# working.net
KiCad netlist of a schematic drawn in EAGLE
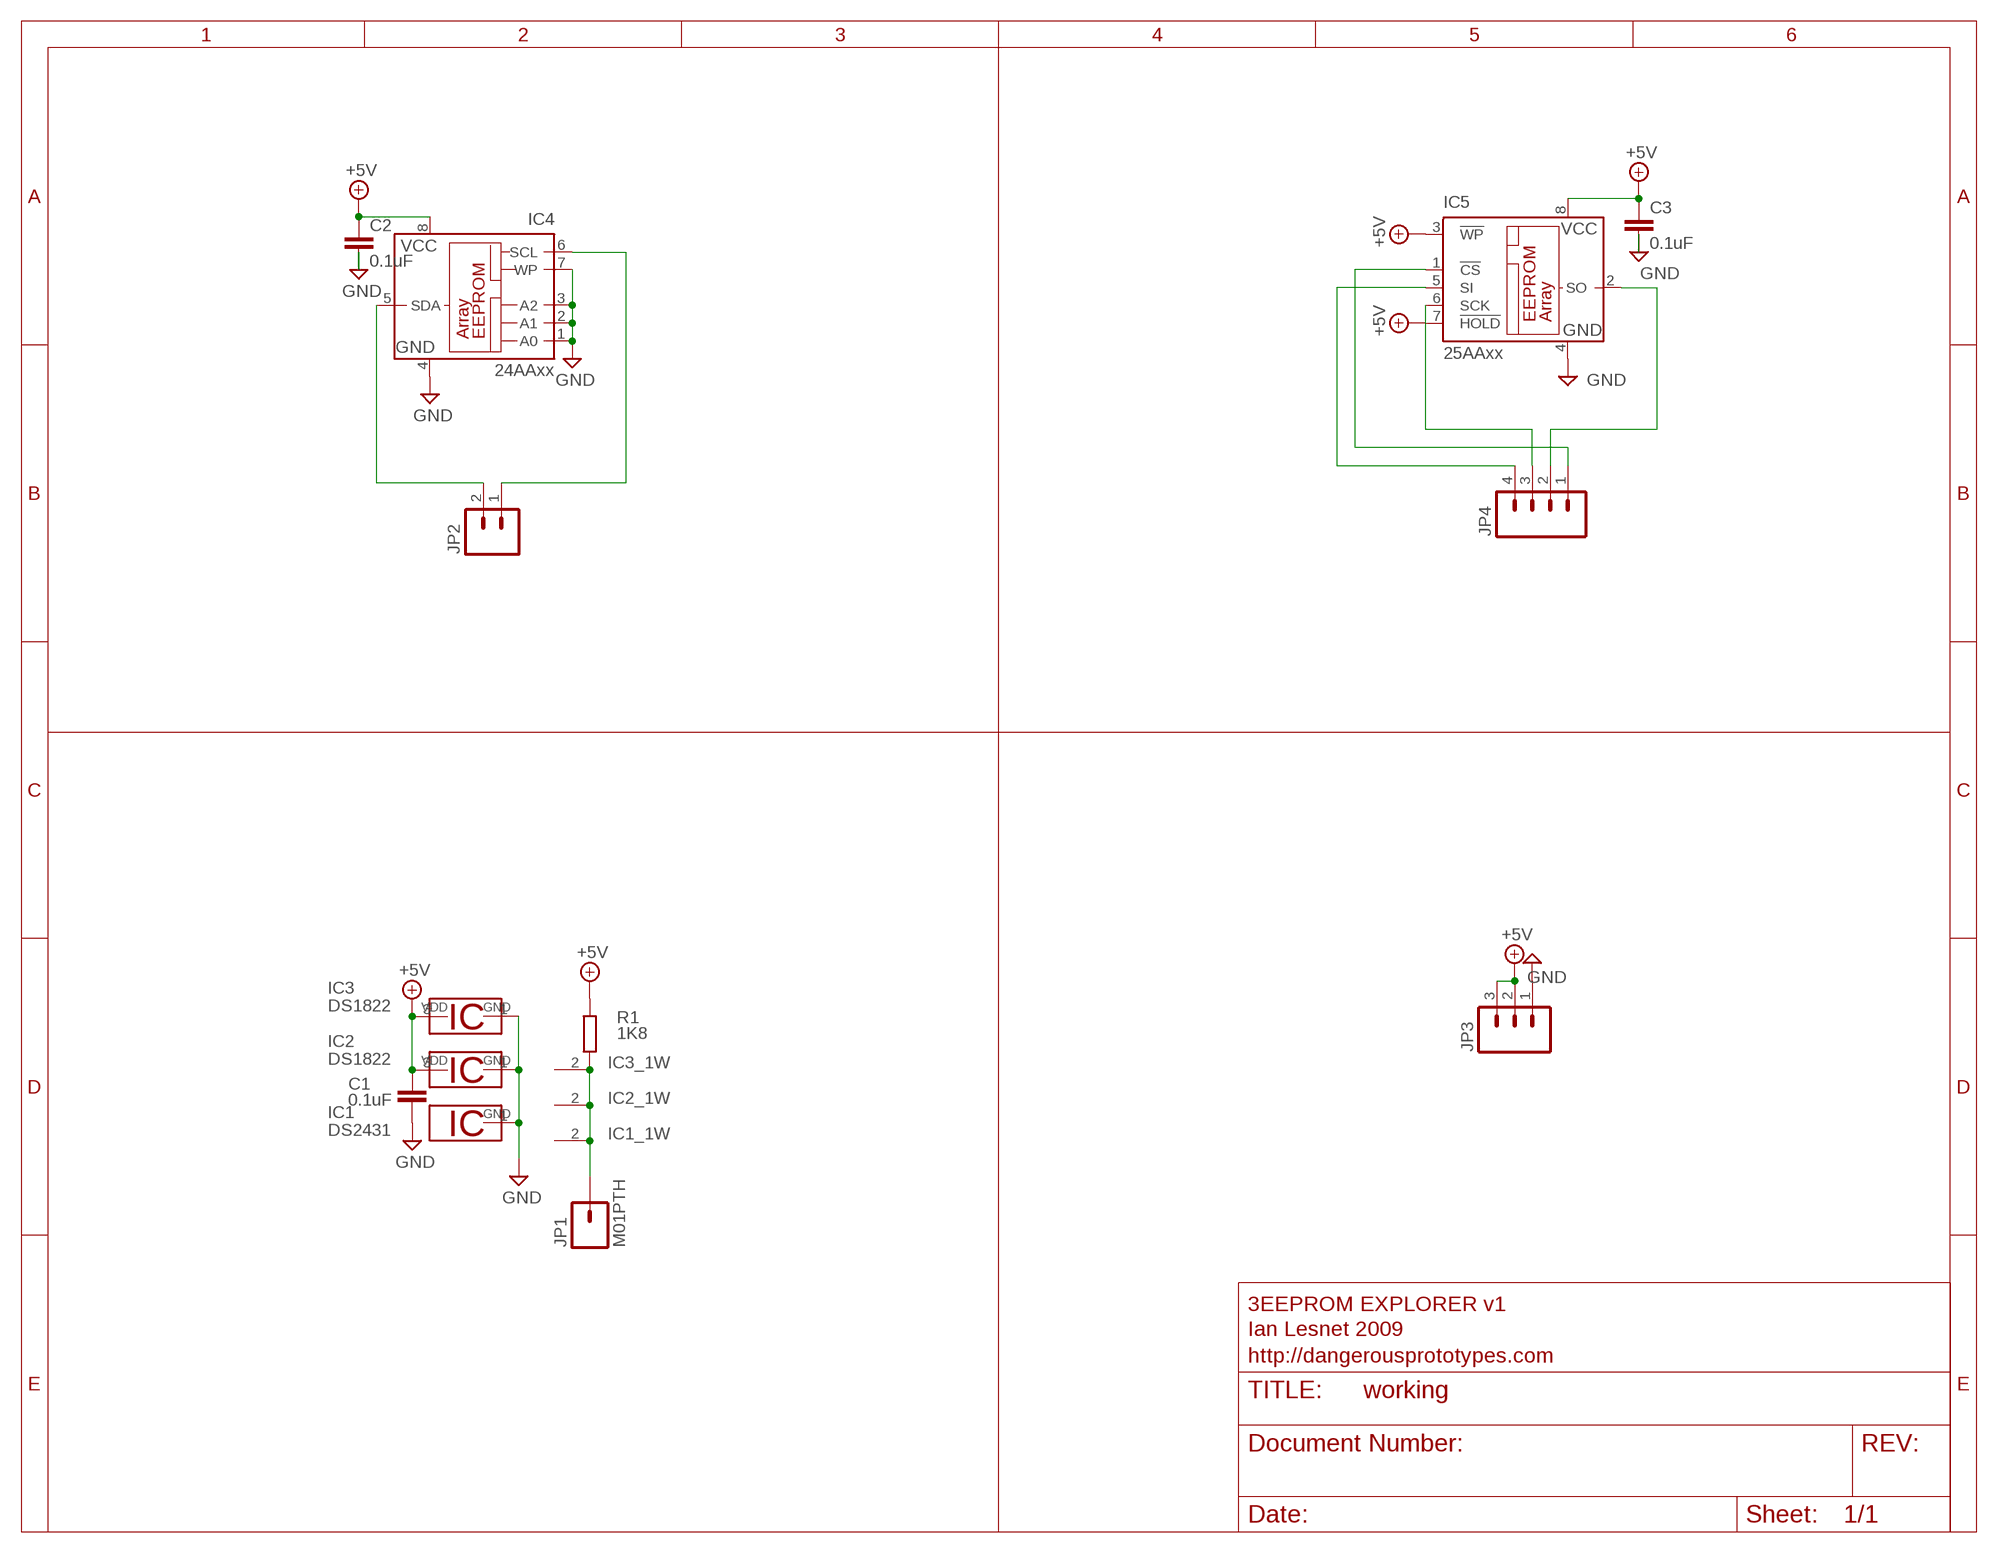
[diagram p0: schematic, sheet 1]

(export (version "E")
  (design (tool "Eeschema 10.0.6"))
  (components
    (comp (ref "C1")
      (value "0.1uF")
      (footprint "eagle-import:C025-025X050")
      (libsource (lib "eagle-import") (part "C-EU025-025X050"))
    )
    (comp (ref "C2")
      (value "0.1uF")
      (footprint "eagle-import:C025-025X050")
      (libsource (lib "eagle-import") (part "C-EU025-025X050"))
    )
    (comp (ref "C3")
      (value "0.1uF")
      (footprint "eagle-import:C025-025X050")
      (libsource (lib "eagle-import") (part "C-EU025-025X050"))
    )
    (comp (ref "IC1")
      (value "DS2431")
      (footprint "eagle-import:TO92-")
      (libsource (lib "eagle-import") (part "DS2431"))
    )
    (comp (ref "IC2")
      (value "DS1822")
      (footprint "eagle-import:TO92-")
      (libsource (lib "eagle-import") (part "DS18S20"))
    )
    (comp (ref "IC3")
      (value "DS1822")
      (footprint "eagle-import:TO92-")
      (libsource (lib "eagle-import") (part "DS18S20"))
    )
    (comp (ref "IC4")
      (value "24AAxx")
      (footprint "eagle-import:DIL8")
      (libsource (lib "eagle-import") (part "24PAA01"))
    )
    (comp (ref "IC5")
      (value "25AAxx")
      (footprint "eagle-import:DIL8")
      (libsource (lib "eagle-import") (part "25PAA040"))
    )
    (comp (ref "JP1")
      (value "M01PTH")
      (footprint "eagle-import:1X01")
      (libsource (lib "eagle-import") (part "M01PTH"))
    )
    (comp (ref "JP2")
      (value "M02PTH")
      (footprint "eagle-import:1X02")
      (libsource (lib "eagle-import") (part "M02PTH"))
    )
    (comp (ref "JP3")
      (value "M03PTH")
      (footprint "eagle-import:1X03")
      (libsource (lib "eagle-import") (part "M03PTH"))
    )
    (comp (ref "JP4")
      (value "M04PTH")
      (footprint "eagle-import:1X04")
      (libsource (lib "eagle-import") (part "M04PTH"))
    )
    (comp (ref "R1")
      (value "1K8")
      (footprint "eagle-import:0204_5")
      (libsource (lib "eagle-import") (part "R-EU_0204/5"))
    )
  )
  (nets
    (net (code "1") (name "+5V") (class "Default")
      (node (ref "C1") (pin "1") (pinfunction "1_1") (pintype "passive"))
      (node (ref "C2") (pin "1") (pinfunction "1_1") (pintype "passive"))
      (node (ref "C3") (pin "1") (pinfunction "1_1") (pintype "passive"))
      (node (ref "IC2") (pin "3") (pinfunction "VDD_3") (pintype "power_in"))
      (node (ref "IC3") (pin "3") (pinfunction "VDD_3") (pintype "power_in"))
      (node (ref "IC4") (pin "8") (pinfunction "VCC_8") (pintype "power_in"))
      (node (ref "IC5") (pin "3") (pinfunction "~{WP}_3") (pintype "input"))
      (node (ref "IC5") (pin "7") (pinfunction "~{HOLD}_7") (pintype "input"))
      (node (ref "IC5") (pin "8") (pinfunction "VCC_8") (pintype "power_in"))
      (node (ref "JP3") (pin "2") (pinfunction "2_2") (pintype "passive"))
      (node (ref "JP3") (pin "3") (pinfunction "3_3") (pintype "passive"))
      (node (ref "R1") (pin "2") (pinfunction "2_2") (pintype "passive"))
    )
    (net (code "2") (name "GND") (class "Default")
      (node (ref "C1") (pin "2") (pinfunction "2_2") (pintype "passive"))
      (node (ref "C2") (pin "2") (pinfunction "2_2") (pintype "passive"))
      (node (ref "C3") (pin "2") (pinfunction "2_2") (pintype "passive"))
      (node (ref "IC1") (pin "1") (pinfunction "GND_1") (pintype "power_in"))
      (node (ref "IC2") (pin "1") (pinfunction "GND_1") (pintype "power_in"))
      (node (ref "IC3") (pin "1") (pinfunction "GND_1") (pintype "power_in"))
      (node (ref "IC4") (pin "1") (pinfunction "A0_1") (pintype "input"))
      (node (ref "IC4") (pin "2") (pinfunction "A1_2") (pintype "input"))
      (node (ref "IC4") (pin "3") (pinfunction "A2_3") (pintype "input"))
      (node (ref "IC4") (pin "4") (pinfunction "GND_4") (pintype "power_in"))
      (node (ref "IC4") (pin "7") (pinfunction "WP_7") (pintype "input"))
      (node (ref "IC5") (pin "4") (pinfunction "GND_4") (pintype "power_in"))
      (node (ref "JP3") (pin "1") (pinfunction "1_1") (pintype "passive"))
    )
    (net (code "3") (name "Net-(IC1C-1W)") (class "Default")
      (node (ref "IC1") (pin "2") (pinfunction "1W_2") (pintype "power_in"))
      (node (ref "IC2") (pin "2") (pinfunction "1W_2") (pintype "power_in"))
      (node (ref "IC3") (pin "2") (pinfunction "1W_2") (pintype "power_in"))
      (node (ref "JP1") (pin "1") (pinfunction "1_1") (pintype "passive"))
      (node (ref "R1") (pin "1") (pinfunction "1_1") (pintype "passive"))
    )
    (net (code "4") (name "Net-(IC4-SCL)") (class "Default")
      (node (ref "IC4") (pin "6") (pinfunction "SCL_6") (pintype "input"))
      (node (ref "JP2") (pin "1") (pinfunction "1_1") (pintype "passive"))
    )
    (net (code "5") (name "Net-(IC4-SDA)") (class "Default")
      (node (ref "IC4") (pin "5") (pinfunction "SDA_5") (pintype "bidirectional"))
      (node (ref "JP2") (pin "2") (pinfunction "2_2") (pintype "passive"))
    )
    (net (code "6") (name "Net-(IC5-SCK)") (class "Default")
      (node (ref "IC5") (pin "6") (pinfunction "SCK_6") (pintype "input"))
      (node (ref "JP4") (pin "3") (pinfunction "3_3") (pintype "passive"))
    )
    (net (code "7") (name "Net-(IC5-SI)") (class "Default")
      (node (ref "IC5") (pin "5") (pinfunction "SI_5") (pintype "input"))
      (node (ref "JP4") (pin "4") (pinfunction "4_4") (pintype "passive"))
    )
    (net (code "8") (name "Net-(IC5-SO)") (class "Default")
      (node (ref "IC5") (pin "2") (pinfunction "SO_2") (pintype "bidirectional"))
      (node (ref "JP4") (pin "2") (pinfunction "2_2") (pintype "passive"))
    )
    (net (code "9") (name "Net-(IC5-~{CS})") (class "Default")
      (node (ref "IC5") (pin "1") (pinfunction "~{CS}_1") (pintype "input"))
      (node (ref "JP4") (pin "1") (pinfunction "1_1") (pintype "passive"))
    )
  )
)
